# PGTN013_halo_fuzz.net
KiCad netlist of a schematic drawn in EAGLE
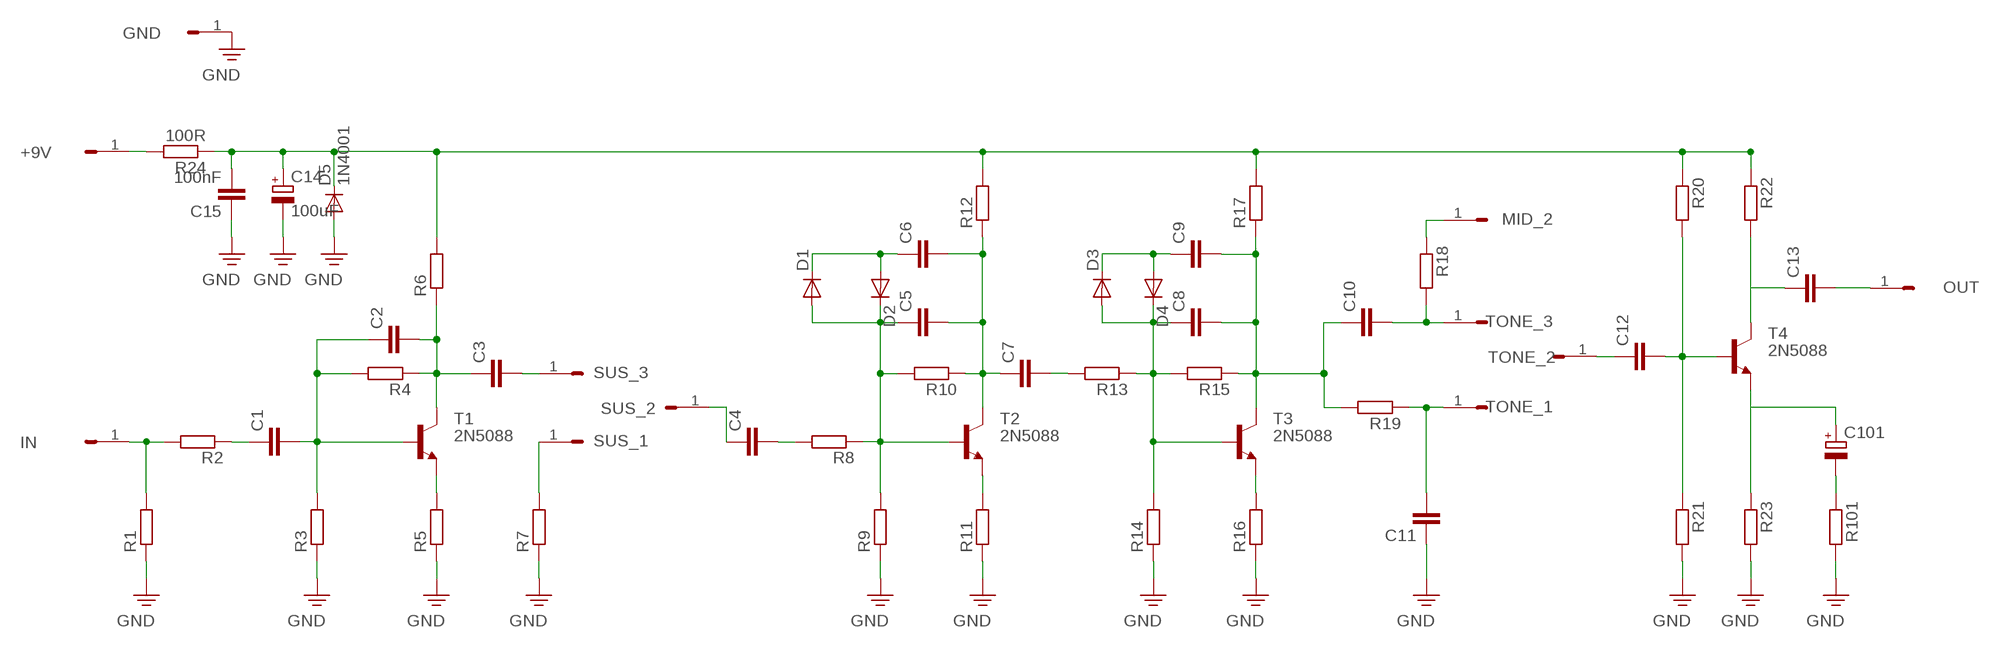
[diagram p0: schematic, sheet 1]

(export (version "E")
  (design (tool "Eeschema 10.0.6"))
  (components
    (comp (ref "+9V")
      (value "HEADER/MALE/01")
      (footprint "eagle-import:HEADER_MALE_01")
      (libsource (lib "eagle-import") (part "HEADER/MALE/01"))
    )
    (comp (ref "C1")
      (value "CAPACITORCERAMICDISC/5")
      (footprint "eagle-import:CERAMICDISC_5")
      (libsource (lib "eagle-import") (part "CAPACITORCERAMICDISC/5"))
    )
    (comp (ref "C2")
      (value "CAPACITORCERAMICDISC/5")
      (footprint "eagle-import:CERAMICDISC_5")
      (libsource (lib "eagle-import") (part "CAPACITORCERAMICDISC/5"))
    )
    (comp (ref "C3")
      (value "CAPACITORCERAMICDISC/5")
      (footprint "eagle-import:CERAMICDISC_5")
      (libsource (lib "eagle-import") (part "CAPACITORCERAMICDISC/5"))
    )
    (comp (ref "C4")
      (value "CAPACITORCERAMICDISC/5")
      (footprint "eagle-import:CERAMICDISC_5")
      (libsource (lib "eagle-import") (part "CAPACITORCERAMICDISC/5"))
    )
    (comp (ref "C5")
      (value "CAPACITORCERAMICDISC/5")
      (footprint "eagle-import:CERAMICDISC_5")
      (libsource (lib "eagle-import") (part "CAPACITORCERAMICDISC/5"))
    )
    (comp (ref "C6")
      (value "CAPACITORCERAMICDISC/5")
      (footprint "eagle-import:CERAMICDISC_5")
      (libsource (lib "eagle-import") (part "CAPACITORCERAMICDISC/5"))
    )
    (comp (ref "C7")
      (value "CAPACITORCERAMICDISC/5")
      (footprint "eagle-import:CERAMICDISC_5")
      (libsource (lib "eagle-import") (part "CAPACITORCERAMICDISC/5"))
    )
    (comp (ref "C8")
      (value "CAPACITORCERAMICDISC/5")
      (footprint "eagle-import:CERAMICDISC_5")
      (libsource (lib "eagle-import") (part "CAPACITORCERAMICDISC/5"))
    )
    (comp (ref "C9")
      (value "CAPACITORCERAMICDISC/5")
      (footprint "eagle-import:CERAMICDISC_5")
      (libsource (lib "eagle-import") (part "CAPACITORCERAMICDISC/5"))
    )
    (comp (ref "C10")
      (value "CAPACITORCERAMICDISC/5")
      (footprint "eagle-import:CERAMICDISC_5")
      (libsource (lib "eagle-import") (part "CAPACITORCERAMICDISC/5"))
    )
    (comp (ref "C11")
      (value "CAPACITORCERAMICDISC/5")
      (footprint "eagle-import:CERAMICDISC_5")
      (libsource (lib "eagle-import") (part "CAPACITORCERAMICDISC/5"))
    )
    (comp (ref "C12")
      (value "CAPACITORCERAMICDISC/5")
      (footprint "eagle-import:CERAMICDISC_5")
      (libsource (lib "eagle-import") (part "CAPACITORCERAMICDISC/5"))
    )
    (comp (ref "C13")
      (value "CAPACITORCERAMICDISC/5")
      (footprint "eagle-import:CERAMICDISC_5")
      (libsource (lib "eagle-import") (part "CAPACITORCERAMICDISC/5"))
    )
    (comp (ref "C14")
      (value "100uF")
      (footprint "eagle-import:E3,5-8")
      (libsource (lib "eagle-import") (part "CAPACITOR/POLARIZEDE3.5-8"))
    )
    (comp (ref "C15")
      (value "100nF")
      (footprint "eagle-import:CERAMICDISC_5")
      (libsource (lib "eagle-import") (part "CAPACITORCERAMICDISC/5"))
    )
    (comp (ref "C101")
      (value "CAPACITOR/POLARIZEDE3.5-8")
      (footprint "eagle-import:E3,5-8")
      (libsource (lib "eagle-import") (part "CAPACITOR/POLARIZEDE3.5-8"))
    )
    (comp (ref "D1")
      (value "1N4148DO35-7")
      (footprint "eagle-import:DO35-7")
      (libsource (lib "eagle-import") (part "1N4148DO35-7"))
    )
    (comp (ref "D2")
      (value "1N4148DO35-7")
      (footprint "eagle-import:DO35-7")
      (libsource (lib "eagle-import") (part "1N4148DO35-7"))
    )
    (comp (ref "D3")
      (value "1N4148DO35-7")
      (footprint "eagle-import:DO35-7")
      (libsource (lib "eagle-import") (part "1N4148DO35-7"))
    )
    (comp (ref "D4")
      (value "1N4148DO35-7")
      (footprint "eagle-import:DO35-7")
      (libsource (lib "eagle-import") (part "1N4148DO35-7"))
    )
    (comp (ref "D5")
      (value "1N4001")
      (footprint "eagle-import:DO35-7")
      (libsource (lib "eagle-import") (part "1N4148DO35-7"))
    )
    (comp (ref "GND")
      (value "HEADER/MALE/01")
      (footprint "eagle-import:HEADER_MALE_01")
      (libsource (lib "eagle-import") (part "HEADER/MALE/01"))
    )
    (comp (ref "IN")
      (value "HEADER/MALE/01")
      (footprint "eagle-import:HEADER_MALE_01")
      (libsource (lib "eagle-import") (part "HEADER/MALE/01"))
    )
    (comp (ref "MID_2")
      (value "HEADER/MALE/01")
      (footprint "eagle-import:HEADER_MALE_01")
      (libsource (lib "eagle-import") (part "HEADER/MALE/01"))
    )
    (comp (ref "OUT")
      (value "HEADER/MALE/01")
      (footprint "eagle-import:HEADER_MALE_01")
      (libsource (lib "eagle-import") (part "HEADER/MALE/01"))
    )
    (comp (ref "R1")
      (value "RESISTORRESISTOR/UPRIGHT/7.5")
      (footprint "eagle-import:RESISTOR_7.5")
      (libsource (lib "eagle-import") (part "RESISTORRESISTOR/UPRIGHT/7.5"))
    )
    (comp (ref "R2")
      (value "RESISTORRESISTOR/UPRIGHT/7.5")
      (footprint "eagle-import:RESISTOR_7.5")
      (libsource (lib "eagle-import") (part "RESISTORRESISTOR/UPRIGHT/7.5"))
    )
    (comp (ref "R3")
      (value "RESISTORRESISTOR/UPRIGHT/7.5")
      (footprint "eagle-import:RESISTOR_7.5")
      (libsource (lib "eagle-import") (part "RESISTORRESISTOR/UPRIGHT/7.5"))
    )
    (comp (ref "R4")
      (value "RESISTORRESISTOR/UPRIGHT/7.5")
      (footprint "eagle-import:RESISTOR_7.5")
      (libsource (lib "eagle-import") (part "RESISTORRESISTOR/UPRIGHT/7.5"))
    )
    (comp (ref "R5")
      (value "RESISTORRESISTOR/UPRIGHT/7.5")
      (footprint "eagle-import:RESISTOR_7.5")
      (libsource (lib "eagle-import") (part "RESISTORRESISTOR/UPRIGHT/7.5"))
    )
    (comp (ref "R6")
      (value "RESISTORRESISTOR/UPRIGHT/7.5")
      (footprint "eagle-import:RESISTOR_7.5")
      (libsource (lib "eagle-import") (part "RESISTORRESISTOR/UPRIGHT/7.5"))
    )
    (comp (ref "R7")
      (value "RESISTORRESISTOR/UPRIGHT/7.5")
      (footprint "eagle-import:RESISTOR_7.5")
      (libsource (lib "eagle-import") (part "RESISTORRESISTOR/UPRIGHT/7.5"))
    )
    (comp (ref "R8")
      (value "RESISTORRESISTOR/UPRIGHT/7.5")
      (footprint "eagle-import:RESISTOR_7.5")
      (libsource (lib "eagle-import") (part "RESISTORRESISTOR/UPRIGHT/7.5"))
    )
    (comp (ref "R9")
      (value "RESISTORRESISTOR/UPRIGHT/7.5")
      (footprint "eagle-import:RESISTOR_7.5")
      (libsource (lib "eagle-import") (part "RESISTORRESISTOR/UPRIGHT/7.5"))
    )
    (comp (ref "R10")
      (value "RESISTORRESISTOR/UPRIGHT/7.5")
      (footprint "eagle-import:RESISTOR_7.5")
      (libsource (lib "eagle-import") (part "RESISTORRESISTOR/UPRIGHT/7.5"))
    )
    (comp (ref "R11")
      (value "RESISTORRESISTOR/UPRIGHT/7.5")
      (footprint "eagle-import:RESISTOR_7.5")
      (libsource (lib "eagle-import") (part "RESISTORRESISTOR/UPRIGHT/7.5"))
    )
    (comp (ref "R12")
      (value "RESISTORRESISTOR/UPRIGHT/7.5")
      (footprint "eagle-import:RESISTOR_7.5")
      (libsource (lib "eagle-import") (part "RESISTORRESISTOR/UPRIGHT/7.5"))
    )
    (comp (ref "R13")
      (value "RESISTORRESISTOR/UPRIGHT/7.5")
      (footprint "eagle-import:RESISTOR_7.5")
      (libsource (lib "eagle-import") (part "RESISTORRESISTOR/UPRIGHT/7.5"))
    )
    (comp (ref "R14")
      (value "RESISTORRESISTOR/UPRIGHT/7.5")
      (footprint "eagle-import:RESISTOR_7.5")
      (libsource (lib "eagle-import") (part "RESISTORRESISTOR/UPRIGHT/7.5"))
    )
    (comp (ref "R15")
      (value "RESISTORRESISTOR/UPRIGHT/7.5")
      (footprint "eagle-import:RESISTOR_7.5")
      (libsource (lib "eagle-import") (part "RESISTORRESISTOR/UPRIGHT/7.5"))
    )
    (comp (ref "R16")
      (value "RESISTORRESISTOR/UPRIGHT/7.5")
      (footprint "eagle-import:RESISTOR_7.5")
      (libsource (lib "eagle-import") (part "RESISTORRESISTOR/UPRIGHT/7.5"))
    )
    (comp (ref "R17")
      (value "RESISTORRESISTOR/UPRIGHT/7.5")
      (footprint "eagle-import:RESISTOR_7.5")
      (libsource (lib "eagle-import") (part "RESISTORRESISTOR/UPRIGHT/7.5"))
    )
    (comp (ref "R18")
      (value "RESISTORRESISTOR/UPRIGHT/7.5")
      (footprint "eagle-import:RESISTOR_7.5")
      (libsource (lib "eagle-import") (part "RESISTORRESISTOR/UPRIGHT/7.5"))
    )
    (comp (ref "R19")
      (value "RESISTORRESISTOR/UPRIGHT/7.5")
      (footprint "eagle-import:RESISTOR_7.5")
      (libsource (lib "eagle-import") (part "RESISTORRESISTOR/UPRIGHT/7.5"))
    )
    (comp (ref "R20")
      (value "RESISTORRESISTOR/UPRIGHT/7.5")
      (footprint "eagle-import:RESISTOR_7.5")
      (libsource (lib "eagle-import") (part "RESISTORRESISTOR/UPRIGHT/7.5"))
    )
    (comp (ref "R21")
      (value "RESISTORRESISTOR/UPRIGHT/7.5")
      (footprint "eagle-import:RESISTOR_7.5")
      (libsource (lib "eagle-import") (part "RESISTORRESISTOR/UPRIGHT/7.5"))
    )
    (comp (ref "R22")
      (value "RESISTORRESISTOR/UPRIGHT/7.5")
      (footprint "eagle-import:RESISTOR_7.5")
      (libsource (lib "eagle-import") (part "RESISTORRESISTOR/UPRIGHT/7.5"))
    )
    (comp (ref "R23")
      (value "RESISTORRESISTOR/UPRIGHT/7.5")
      (footprint "eagle-import:RESISTOR_7.5")
      (libsource (lib "eagle-import") (part "RESISTORRESISTOR/UPRIGHT/7.5"))
    )
    (comp (ref "R24")
      (value "100R")
      (footprint "eagle-import:RESISTOR_7.5")
      (libsource (lib "eagle-import") (part "RESISTORRESISTOR/UPRIGHT/7.5"))
    )
    (comp (ref "R101")
      (value "RESISTORRESISTOR/UPRIGHT/7.5")
      (footprint "eagle-import:RESISTOR_7.5")
      (libsource (lib "eagle-import") (part "RESISTORRESISTOR/UPRIGHT/7.5"))
    )
    (comp (ref "SUS_1")
      (value "HEADER/MALE/01")
      (footprint "eagle-import:HEADER_MALE_01")
      (libsource (lib "eagle-import") (part "HEADER/MALE/01"))
    )
    (comp (ref "SUS_2")
      (value "HEADER/MALE/01")
      (footprint "eagle-import:HEADER_MALE_01")
      (libsource (lib "eagle-import") (part "HEADER/MALE/01"))
    )
    (comp (ref "SUS_3")
      (value "HEADER/MALE/01")
      (footprint "eagle-import:HEADER_MALE_01")
      (libsource (lib "eagle-import") (part "HEADER/MALE/01"))
    )
    (comp (ref "T1")
      (value "2N5088")
      (footprint "eagle-import:TO92")
      (libsource (lib "eagle-import") (part "2N5088"))
    )
    (comp (ref "T2")
      (value "2N5088")
      (footprint "eagle-import:TO92")
      (libsource (lib "eagle-import") (part "2N5088"))
    )
    (comp (ref "T3")
      (value "2N5088")
      (footprint "eagle-import:TO92")
      (libsource (lib "eagle-import") (part "2N5088"))
    )
    (comp (ref "T4")
      (value "2N5088")
      (footprint "eagle-import:TO92")
      (libsource (lib "eagle-import") (part "2N5088"))
    )
    (comp (ref "TONE_1")
      (value "HEADER/MALE/01")
      (footprint "eagle-import:HEADER_MALE_01")
      (libsource (lib "eagle-import") (part "HEADER/MALE/01"))
    )
    (comp (ref "TONE_2")
      (value "HEADER/MALE/01")
      (footprint "eagle-import:HEADER_MALE_01")
      (libsource (lib "eagle-import") (part "HEADER/MALE/01"))
    )
    (comp (ref "TONE_3")
      (value "HEADER/MALE/01")
      (footprint "eagle-import:HEADER_MALE_01")
      (libsource (lib "eagle-import") (part "HEADER/MALE/01"))
    )
  )
  (nets
    (net (code "1") (name "GND") (class "Default")
      (node (ref "C11") (pin "1") (pinfunction "1_1") (pintype "passive"))
      (node (ref "C14") (pin "-") (pinfunction "-_-") (pintype "passive"))
      (node (ref "C15") (pin "1") (pinfunction "1_1") (pintype "passive"))
      (node (ref "D5") (pin "A") (pinfunction "A_A") (pintype "passive"))
      (node (ref "GND") (pin "1") (pinfunction "3_1") (pintype "passive"))
      (node (ref "R1") (pin "1") (pinfunction "1_1") (pintype "passive"))
      (node (ref "R101") (pin "2") (pinfunction "2_2") (pintype "passive"))
      (node (ref "R11") (pin "1") (pinfunction "1_1") (pintype "passive"))
      (node (ref "R14") (pin "1") (pinfunction "1_1") (pintype "passive"))
      (node (ref "R16") (pin "1") (pinfunction "1_1") (pintype "passive"))
      (node (ref "R21") (pin "2") (pinfunction "2_2") (pintype "passive"))
      (node (ref "R23") (pin "2") (pinfunction "2_2") (pintype "passive"))
      (node (ref "R3") (pin "1") (pinfunction "1_1") (pintype "passive"))
      (node (ref "R5") (pin "1") (pinfunction "1_1") (pintype "passive"))
      (node (ref "R7") (pin "1") (pinfunction "1_1") (pintype "passive"))
      (node (ref "R9") (pin "1") (pinfunction "1_1") (pintype "passive"))
    )
    (net (code "2") (name "Net-(+9V-3)") (class "Default")
      (node (ref "+9V") (pin "1") (pinfunction "3_1") (pintype "passive"))
      (node (ref "R24") (pin "2") (pinfunction "2_2") (pintype "passive"))
    )
    (net (code "3") (name "Net-(C1-Pad1)") (class "Default")
      (node (ref "C1") (pin "1") (pinfunction "1_1") (pintype "passive"))
      (node (ref "R2") (pin "1") (pinfunction "1_1") (pintype "passive"))
    )
    (net (code "4") (name "Net-(C4-Pad2)") (class "Default")
      (node (ref "C4") (pin "2") (pinfunction "2_2") (pintype "passive"))
      (node (ref "R8") (pin "2") (pinfunction "2_2") (pintype "passive"))
    )
    (net (code "5") (name "Net-(C6-Pad1)") (class "Default")
      (node (ref "C6") (pin "1") (pinfunction "1_1") (pintype "passive"))
      (node (ref "D1") (pin "C") (pinfunction "C_C") (pintype "passive"))
      (node (ref "D2") (pin "A") (pinfunction "A_A") (pintype "passive"))
    )
    (net (code "6") (name "Net-(C7-Pad2)") (class "Default")
      (node (ref "C7") (pin "2") (pinfunction "2_2") (pintype "passive"))
      (node (ref "R13") (pin "2") (pinfunction "2_2") (pintype "passive"))
    )
    (net (code "7") (name "Net-(C9-Pad1)") (class "Default")
      (node (ref "C9") (pin "1") (pinfunction "1_1") (pintype "passive"))
      (node (ref "D3") (pin "C") (pinfunction "C_C") (pintype "passive"))
      (node (ref "D4") (pin "A") (pinfunction "A_A") (pintype "passive"))
    )
    (net (code "8") (name "Net-(C14-Pad+)") (class "Default")
      (node (ref "C14") (pin "+") (pinfunction "+_+") (pintype "passive"))
      (node (ref "C15") (pin "2") (pinfunction "2_2") (pintype "passive"))
      (node (ref "D5") (pin "C") (pinfunction "C_C") (pintype "passive"))
      (node (ref "R12") (pin "2") (pinfunction "2_2") (pintype "passive"))
      (node (ref "R17") (pin "2") (pinfunction "2_2") (pintype "passive"))
      (node (ref "R20") (pin "1") (pinfunction "1_1") (pintype "passive"))
      (node (ref "R22") (pin "1") (pinfunction "1_1") (pintype "passive"))
      (node (ref "R24") (pin "1") (pinfunction "1_1") (pintype "passive"))
      (node (ref "R6") (pin "2") (pinfunction "2_2") (pintype "passive"))
    )
    (net (code "9") (name "Net-(C101-Pad-)") (class "Default")
      (node (ref "C101") (pin "-") (pinfunction "-_-") (pintype "passive"))
      (node (ref "R101") (pin "1") (pinfunction "1_1") (pintype "passive"))
    )
    (net (code "10") (name "Net-(IN-3)") (class "Default")
      (node (ref "IN") (pin "1") (pinfunction "3_1") (pintype "passive"))
      (node (ref "R1") (pin "2") (pinfunction "2_2") (pintype "passive"))
      (node (ref "R2") (pin "2") (pinfunction "2_2") (pintype "passive"))
    )
    (net (code "11") (name "Net-(MID_2-3)") (class "Default")
      (node (ref "MID_2") (pin "1") (pinfunction "3_1") (pintype "passive"))
      (node (ref "R18") (pin "1") (pinfunction "1_1") (pintype "passive"))
    )
    (net (code "12") (name "Net-(OUT-3)") (class "Default")
      (node (ref "C13") (pin "2") (pinfunction "2_2") (pintype "passive"))
      (node (ref "OUT") (pin "1") (pinfunction "3_1") (pintype "passive"))
    )
    (net (code "13") (name "Net-(SUS_1-3)") (class "Default")
      (node (ref "R7") (pin "2") (pinfunction "2_2") (pintype "passive"))
      (node (ref "SUS_1") (pin "1") (pinfunction "3_1") (pintype "passive"))
    )
    (net (code "14") (name "Net-(SUS_2-3)") (class "Default")
      (node (ref "C4") (pin "1") (pinfunction "1_1") (pintype "passive"))
      (node (ref "SUS_2") (pin "1") (pinfunction "3_1") (pintype "passive"))
    )
    (net (code "15") (name "Net-(SUS_3-3)") (class "Default")
      (node (ref "C3") (pin "2") (pinfunction "2_2") (pintype "passive"))
      (node (ref "SUS_3") (pin "1") (pinfunction "3_1") (pintype "passive"))
    )
    (net (code "16") (name "Net-(T1-B)") (class "Default")
      (node (ref "C1") (pin "2") (pinfunction "2_2") (pintype "passive"))
      (node (ref "C2") (pin "1") (pinfunction "1_1") (pintype "passive"))
      (node (ref "R3") (pin "2") (pinfunction "2_2") (pintype "passive"))
      (node (ref "R4") (pin "2") (pinfunction "2_2") (pintype "passive"))
      (node (ref "T1") (pin "2") (pinfunction "B_2") (pintype "passive"))
    )
    (net (code "17") (name "Net-(T1-C)") (class "Default")
      (node (ref "C2") (pin "2") (pinfunction "2_2") (pintype "passive"))
      (node (ref "C3") (pin "1") (pinfunction "1_1") (pintype "passive"))
      (node (ref "R4") (pin "1") (pinfunction "1_1") (pintype "passive"))
      (node (ref "R6") (pin "1") (pinfunction "1_1") (pintype "passive"))
      (node (ref "T1") (pin "1") (pinfunction "C_1") (pintype "passive"))
    )
    (net (code "18") (name "Net-(T1-E)") (class "Default")
      (node (ref "R5") (pin "2") (pinfunction "2_2") (pintype "passive"))
      (node (ref "T1") (pin "3") (pinfunction "E_3") (pintype "passive"))
    )
    (net (code "19") (name "Net-(T2-B)") (class "Default")
      (node (ref "C5") (pin "1") (pinfunction "1_1") (pintype "passive"))
      (node (ref "D1") (pin "A") (pinfunction "A_A") (pintype "passive"))
      (node (ref "D2") (pin "C") (pinfunction "C_C") (pintype "passive"))
      (node (ref "R10") (pin "2") (pinfunction "2_2") (pintype "passive"))
      (node (ref "R8") (pin "1") (pinfunction "1_1") (pintype "passive"))
      (node (ref "R9") (pin "2") (pinfunction "2_2") (pintype "passive"))
      (node (ref "T2") (pin "2") (pinfunction "B_2") (pintype "passive"))
    )
    (net (code "20") (name "Net-(T2-C)") (class "Default")
      (node (ref "C5") (pin "2") (pinfunction "2_2") (pintype "passive"))
      (node (ref "C6") (pin "2") (pinfunction "2_2") (pintype "passive"))
      (node (ref "C7") (pin "1") (pinfunction "1_1") (pintype "passive"))
      (node (ref "R10") (pin "1") (pinfunction "1_1") (pintype "passive"))
      (node (ref "R12") (pin "1") (pinfunction "1_1") (pintype "passive"))
      (node (ref "T2") (pin "1") (pinfunction "C_1") (pintype "passive"))
    )
    (net (code "21") (name "Net-(T2-E)") (class "Default")
      (node (ref "R11") (pin "2") (pinfunction "2_2") (pintype "passive"))
      (node (ref "T2") (pin "3") (pinfunction "E_3") (pintype "passive"))
    )
    (net (code "22") (name "Net-(T3-B)") (class "Default")
      (node (ref "C8") (pin "1") (pinfunction "1_1") (pintype "passive"))
      (node (ref "D3") (pin "A") (pinfunction "A_A") (pintype "passive"))
      (node (ref "D4") (pin "C") (pinfunction "C_C") (pintype "passive"))
      (node (ref "R13") (pin "1") (pinfunction "1_1") (pintype "passive"))
      (node (ref "R14") (pin "2") (pinfunction "2_2") (pintype "passive"))
      (node (ref "R15") (pin "2") (pinfunction "2_2") (pintype "passive"))
      (node (ref "T3") (pin "2") (pinfunction "B_2") (pintype "passive"))
    )
    (net (code "23") (name "Net-(T3-C)") (class "Default")
      (node (ref "C10") (pin "1") (pinfunction "1_1") (pintype "passive"))
      (node (ref "C8") (pin "2") (pinfunction "2_2") (pintype "passive"))
      (node (ref "C9") (pin "2") (pinfunction "2_2") (pintype "passive"))
      (node (ref "R15") (pin "1") (pinfunction "1_1") (pintype "passive"))
      (node (ref "R17") (pin "1") (pinfunction "1_1") (pintype "passive"))
      (node (ref "R19") (pin "2") (pinfunction "2_2") (pintype "passive"))
      (node (ref "T3") (pin "1") (pinfunction "C_1") (pintype "passive"))
    )
    (net (code "24") (name "Net-(T3-E)") (class "Default")
      (node (ref "R16") (pin "2") (pinfunction "2_2") (pintype "passive"))
      (node (ref "T3") (pin "3") (pinfunction "E_3") (pintype "passive"))
    )
    (net (code "25") (name "Net-(T4-B)") (class "Default")
      (node (ref "C12") (pin "2") (pinfunction "2_2") (pintype "passive"))
      (node (ref "R20") (pin "2") (pinfunction "2_2") (pintype "passive"))
      (node (ref "R21") (pin "1") (pinfunction "1_1") (pintype "passive"))
      (node (ref "T4") (pin "2") (pinfunction "B_2") (pintype "passive"))
    )
    (net (code "26") (name "Net-(T4-C)") (class "Default")
      (node (ref "C13") (pin "1") (pinfunction "1_1") (pintype "passive"))
      (node (ref "R22") (pin "2") (pinfunction "2_2") (pintype "passive"))
      (node (ref "T4") (pin "1") (pinfunction "C_1") (pintype "passive"))
    )
    (net (code "27") (name "Net-(T4-E)") (class "Default")
      (node (ref "C101") (pin "+") (pinfunction "+_+") (pintype "passive"))
      (node (ref "R23") (pin "1") (pinfunction "1_1") (pintype "passive"))
      (node (ref "T4") (pin "3") (pinfunction "E_3") (pintype "passive"))
    )
    (net (code "28") (name "Net-(TONE_1-3)") (class "Default")
      (node (ref "C11") (pin "2") (pinfunction "2_2") (pintype "passive"))
      (node (ref "R19") (pin "1") (pinfunction "1_1") (pintype "passive"))
      (node (ref "TONE_1") (pin "1") (pinfunction "3_1") (pintype "passive"))
    )
    (net (code "29") (name "Net-(TONE_2-3)") (class "Default")
      (node (ref "C12") (pin "1") (pinfunction "1_1") (pintype "passive"))
      (node (ref "TONE_2") (pin "1") (pinfunction "3_1") (pintype "passive"))
    )
    (net (code "30") (name "Net-(TONE_3-3)") (class "Default")
      (node (ref "C10") (pin "2") (pinfunction "2_2") (pintype "passive"))
      (node (ref "R18") (pin "2") (pinfunction "2_2") (pintype "passive"))
      (node (ref "TONE_3") (pin "1") (pinfunction "3_1") (pintype "passive"))
    )
  )
)
